# ADXL_ADXRS_Breakout_Pod_RevB.net
KiCad netlist of a schematic drawn in EAGLE
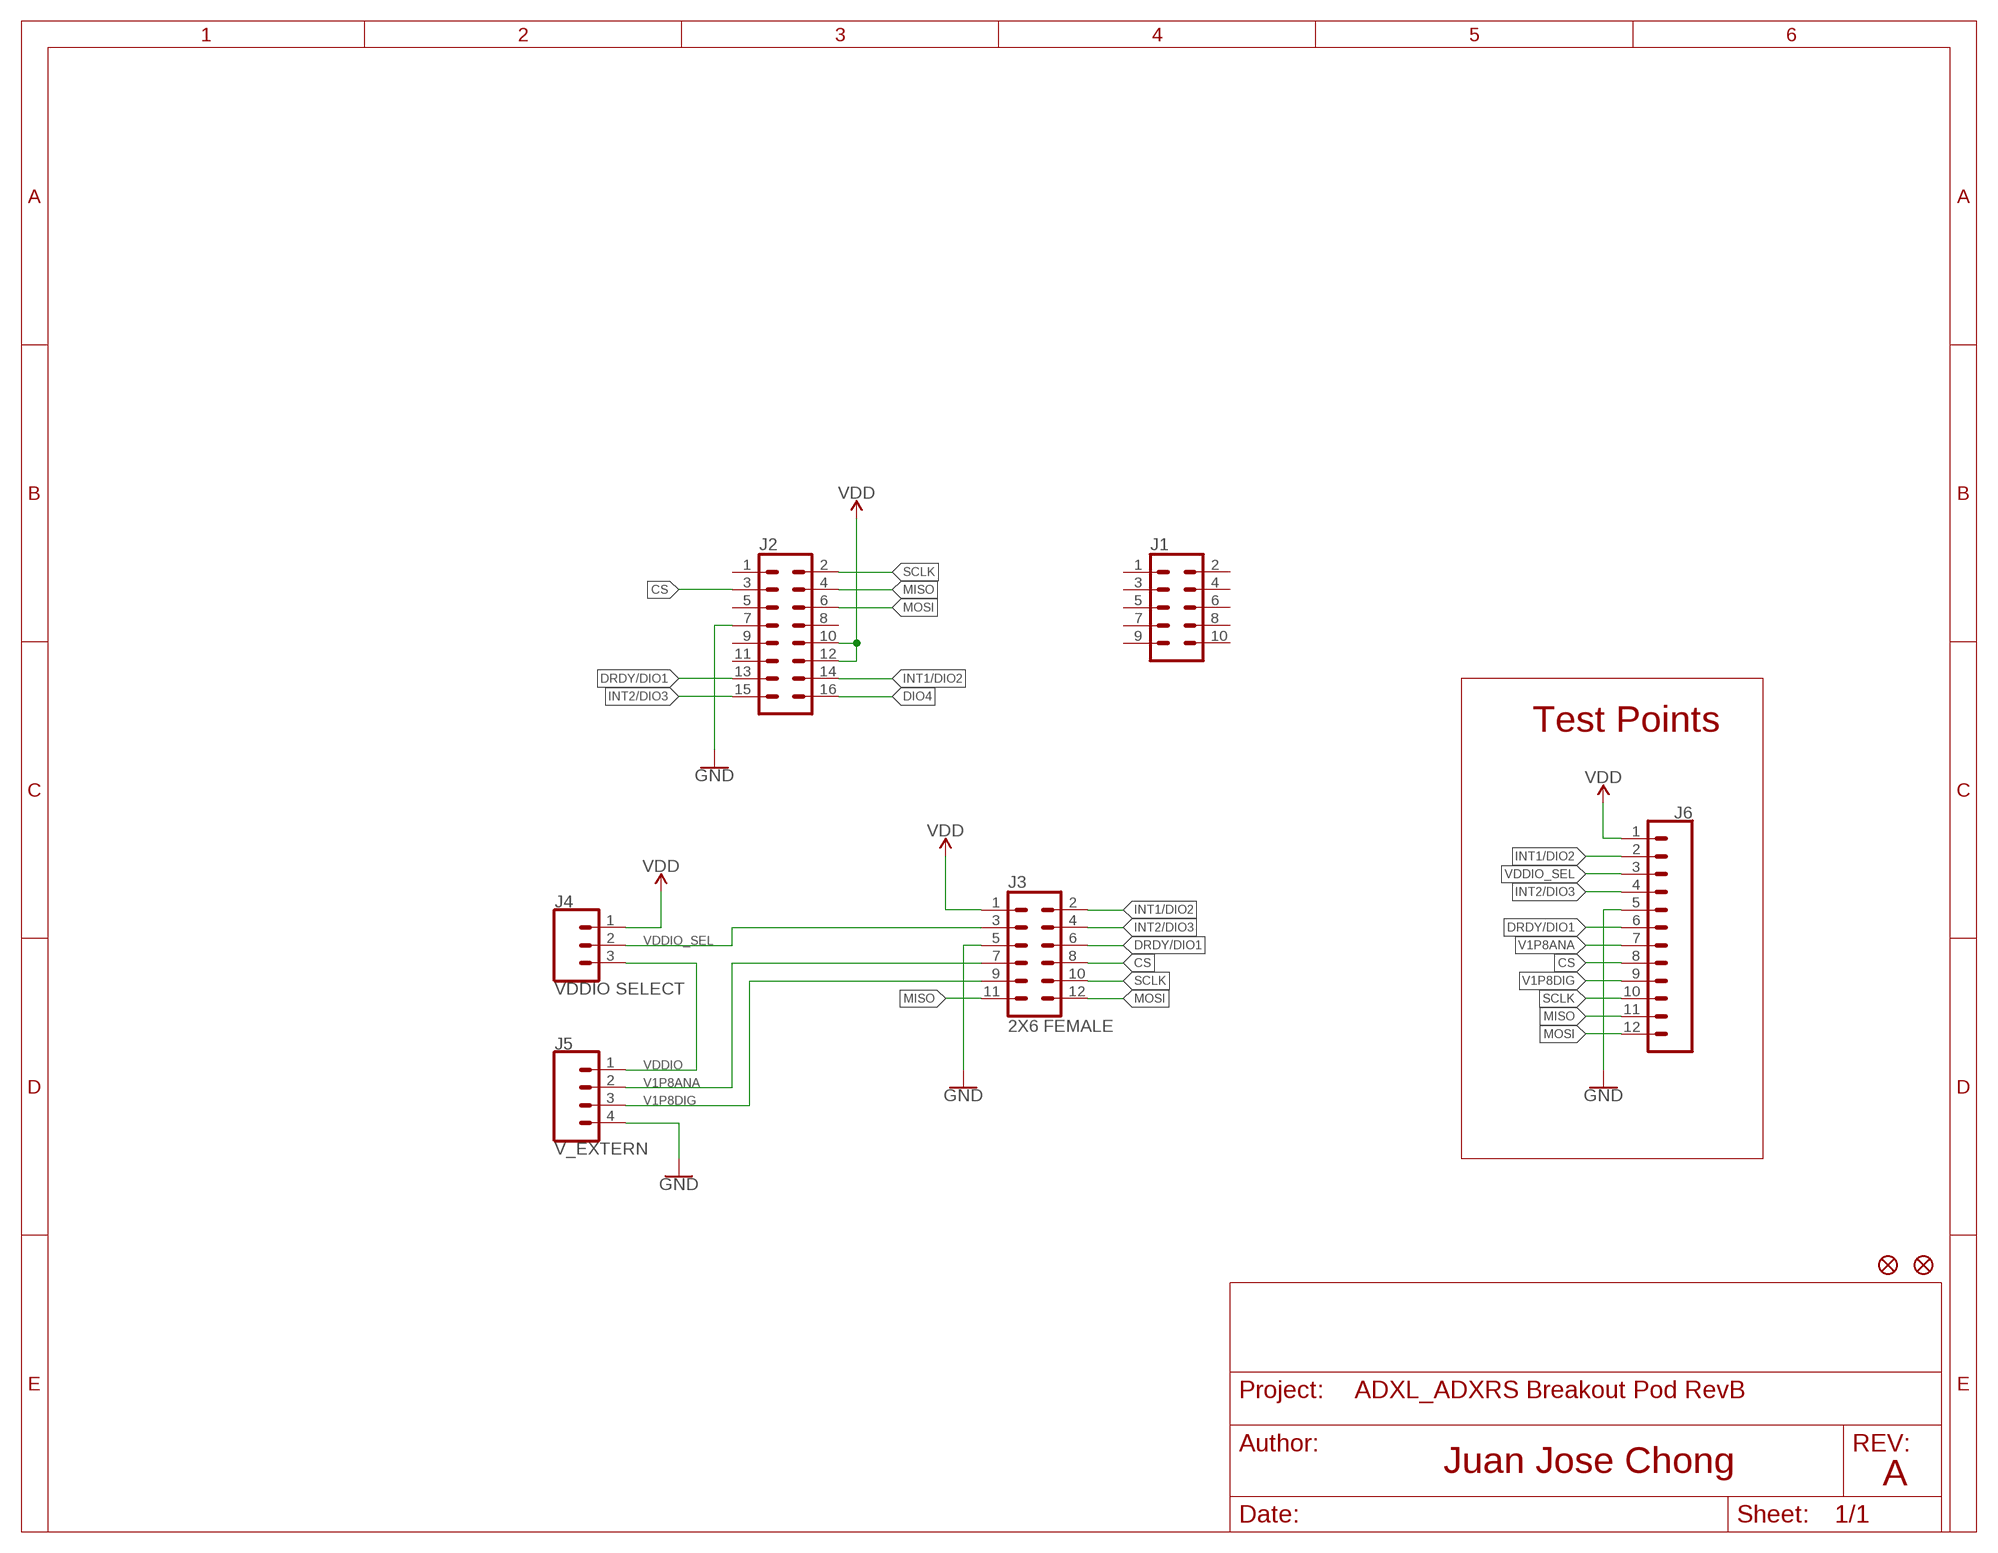
[diagram p0: schematic, sheet 1]

(export (version "E")
  (design (tool "Eeschema 10.0.6"))
  (components
    (comp (ref "FD1")
      (value "FIDUCIAL1X2")
      (footprint "eagle-import:FIDUCIAL-1X2")
      (libsource (lib "eagle-import") (part "FIDUCIAL1X2"))
    )
    (comp (ref "FD2")
      (value "FIDUCIAL1X2")
      (footprint "eagle-import:FIDUCIAL-1X2")
      (libsource (lib "eagle-import") (part "FIDUCIAL1X2"))
    )
    (comp (ref "J1")
      (value "CONN_05X2_2MM_FEMALE")
      (footprint "eagle-import:M22-6550542R")
      (libsource (lib "eagle-import") (part "CONN_05X2_2MM_FEMALE"))
    )
    (comp (ref "J2")
      (value "CONN_08X2_2MM_FEMALE")
      (footprint "eagle-import:M22-6550842R")
      (libsource (lib "eagle-import") (part "CONN_08X2_2MM_FEMALE"))
    )
    (comp (ref "J3")
      (value "2X6 FEMALE")
      (footprint "eagle-import:2X6")
      (libsource (lib "eagle-import") (part "CONN_06X2PTH_FEMALE"))
    )
    (comp (ref "J4")
      (value "VDDIO SELECT")
      (footprint "eagle-import:1X03")
      (libsource (lib "eagle-import") (part "CONN_03"))
    )
    (comp (ref "J5")
      (value "V_EXTERN")
      (footprint "eagle-import:1X04")
      (libsource (lib "eagle-import") (part "CONN_04PTH"))
    )
    (comp (ref "J6")
      (value "CONN_12")
      (footprint "eagle-import:1X12")
      (libsource (lib "eagle-import") (part "CONN_12"))
    )
  )
  (nets
    (net (code "1") (name "/VDDIO") (class "Default")
      (node (ref "J4") (pin "3") (pinfunction "3_3") (pintype "passive"))
      (node (ref "J5") (pin "1") (pinfunction "1_1") (pintype "passive"))
    )
    (net (code "2") (name "CS") (class "Default")
      (node (ref "J2") (pin "3") (pinfunction "3_3") (pintype "passive"))
      (node (ref "J3") (pin "8") (pinfunction "8_8") (pintype "passive"))
      (node (ref "J6") (pin "8") (pinfunction "8_8") (pintype "passive"))
    )
    (net (code "3") (name "DIO4") (class "Default")
      (node (ref "J2") (pin "16") (pinfunction "16_16") (pintype "passive"))
    )
    (net (code "4") (name "DRDY{slash}DIO1") (class "Default")
      (node (ref "J2") (pin "13") (pinfunction "13_13") (pintype "passive"))
      (node (ref "J3") (pin "6") (pinfunction "6_6") (pintype "passive"))
      (node (ref "J6") (pin "6") (pinfunction "6_6") (pintype "passive"))
    )
    (net (code "5") (name "GND") (class "Default")
      (node (ref "J2") (pin "7") (pinfunction "7_7") (pintype "passive"))
      (node (ref "J3") (pin "5") (pinfunction "5_5") (pintype "passive"))
      (node (ref "J5") (pin "4") (pinfunction "4_4") (pintype "passive"))
      (node (ref "J6") (pin "5") (pinfunction "5_5") (pintype "passive"))
    )
    (net (code "6") (name "INT1{slash}DIO2") (class "Default")
      (node (ref "J2") (pin "14") (pinfunction "14_14") (pintype "passive"))
      (node (ref "J3") (pin "2") (pinfunction "2_2") (pintype "passive"))
      (node (ref "J6") (pin "2") (pinfunction "2_2") (pintype "passive"))
    )
    (net (code "7") (name "INT2{slash}DIO3") (class "Default")
      (node (ref "J2") (pin "15") (pinfunction "15_15") (pintype "passive"))
      (node (ref "J3") (pin "4") (pinfunction "4_4") (pintype "passive"))
      (node (ref "J6") (pin "4") (pinfunction "4_4") (pintype "passive"))
    )
    (net (code "8") (name "MISO") (class "Default")
      (node (ref "J2") (pin "4") (pinfunction "4_4") (pintype "passive"))
      (node (ref "J3") (pin "11") (pinfunction "11_11") (pintype "passive"))
      (node (ref "J6") (pin "11") (pinfunction "11_11") (pintype "passive"))
    )
    (net (code "9") (name "MOSI") (class "Default")
      (node (ref "J2") (pin "6") (pinfunction "6_6") (pintype "passive"))
      (node (ref "J3") (pin "12") (pinfunction "12_12") (pintype "passive"))
      (node (ref "J6") (pin "12") (pinfunction "12_12") (pintype "passive"))
    )
    (net (code "10") (name "SCLK") (class "Default")
      (node (ref "J2") (pin "2") (pinfunction "2_2") (pintype "passive"))
      (node (ref "J3") (pin "10") (pinfunction "10_10") (pintype "passive"))
      (node (ref "J6") (pin "10") (pinfunction "10_10") (pintype "passive"))
    )
    (net (code "11") (name "V1P8ANA") (class "Default")
      (node (ref "J3") (pin "7") (pinfunction "7_7") (pintype "passive"))
      (node (ref "J5") (pin "2") (pinfunction "2_2") (pintype "passive"))
      (node (ref "J6") (pin "7") (pinfunction "7_7") (pintype "passive"))
    )
    (net (code "12") (name "V1P8DIG") (class "Default")
      (node (ref "J3") (pin "9") (pinfunction "9_9") (pintype "passive"))
      (node (ref "J5") (pin "3") (pinfunction "3_3") (pintype "passive"))
      (node (ref "J6") (pin "9") (pinfunction "9_9") (pintype "passive"))
    )
    (net (code "13") (name "VDD") (class "Default")
      (node (ref "J2") (pin "10") (pinfunction "10_10") (pintype "passive"))
      (node (ref "J2") (pin "12") (pinfunction "12_12") (pintype "passive"))
      (node (ref "J3") (pin "1") (pinfunction "1_1") (pintype "passive"))
      (node (ref "J4") (pin "1") (pinfunction "1_1") (pintype "passive"))
      (node (ref "J6") (pin "1") (pinfunction "1_1") (pintype "passive"))
    )
    (net (code "14") (name "VDDIO_SEL") (class "Default")
      (node (ref "J3") (pin "3") (pinfunction "3_3") (pintype "passive"))
      (node (ref "J4") (pin "2") (pinfunction "2_2") (pintype "passive"))
      (node (ref "J6") (pin "3") (pinfunction "3_3") (pintype "passive"))
    )
    (net (code "15") (name "unconnected-(J1-Pad1)") (class "Default")
      (node (ref "J1") (pin "1") (pinfunction "1_1") (pintype "passive"))
    )
    (net (code "16") (name "unconnected-(J1-Pad2)") (class "Default")
      (node (ref "J1") (pin "2") (pinfunction "2_2") (pintype "passive"))
    )
    (net (code "17") (name "unconnected-(J1-Pad3)") (class "Default")
      (node (ref "J1") (pin "3") (pinfunction "3_3") (pintype "passive"))
    )
    (net (code "18") (name "unconnected-(J1-Pad4)") (class "Default")
      (node (ref "J1") (pin "4") (pinfunction "4_4") (pintype "passive"))
    )
    (net (code "19") (name "unconnected-(J1-Pad5)") (class "Default")
      (node (ref "J1") (pin "5") (pinfunction "5_5") (pintype "passive"))
    )
    (net (code "20") (name "unconnected-(J1-Pad6)") (class "Default")
      (node (ref "J1") (pin "6") (pinfunction "6_6") (pintype "passive"))
    )
    (net (code "21") (name "unconnected-(J1-Pad7)") (class "Default")
      (node (ref "J1") (pin "7") (pinfunction "7_7") (pintype "passive"))
    )
    (net (code "22") (name "unconnected-(J1-Pad8)") (class "Default")
      (node (ref "J1") (pin "8") (pinfunction "8_8") (pintype "passive"))
    )
    (net (code "23") (name "unconnected-(J1-Pad9)") (class "Default")
      (node (ref "J1") (pin "9") (pinfunction "9_9") (pintype "passive"))
    )
    (net (code "24") (name "unconnected-(J1-Pad10)") (class "Default")
      (node (ref "J1") (pin "10") (pinfunction "10_10") (pintype "passive"))
    )
    (net (code "25") (name "unconnected-(J2-Pad1)") (class "Default")
      (node (ref "J2") (pin "1") (pinfunction "1_1") (pintype "passive"))
    )
    (net (code "26") (name "unconnected-(J2-Pad5)") (class "Default")
      (node (ref "J2") (pin "5") (pinfunction "5_5") (pintype "passive"))
    )
    (net (code "27") (name "unconnected-(J2-Pad8)") (class "Default")
      (node (ref "J2") (pin "8") (pinfunction "8_8") (pintype "passive"))
    )
    (net (code "28") (name "unconnected-(J2-Pad9)") (class "Default")
      (node (ref "J2") (pin "9") (pinfunction "9_9") (pintype "passive"))
    )
    (net (code "29") (name "unconnected-(J2-Pad11)") (class "Default")
      (node (ref "J2") (pin "11") (pinfunction "11_11") (pintype "passive"))
    )
  )
)
